# Mynd_USB_JACK.net
KiCad netlist of a schematic drawn in Altium Designer
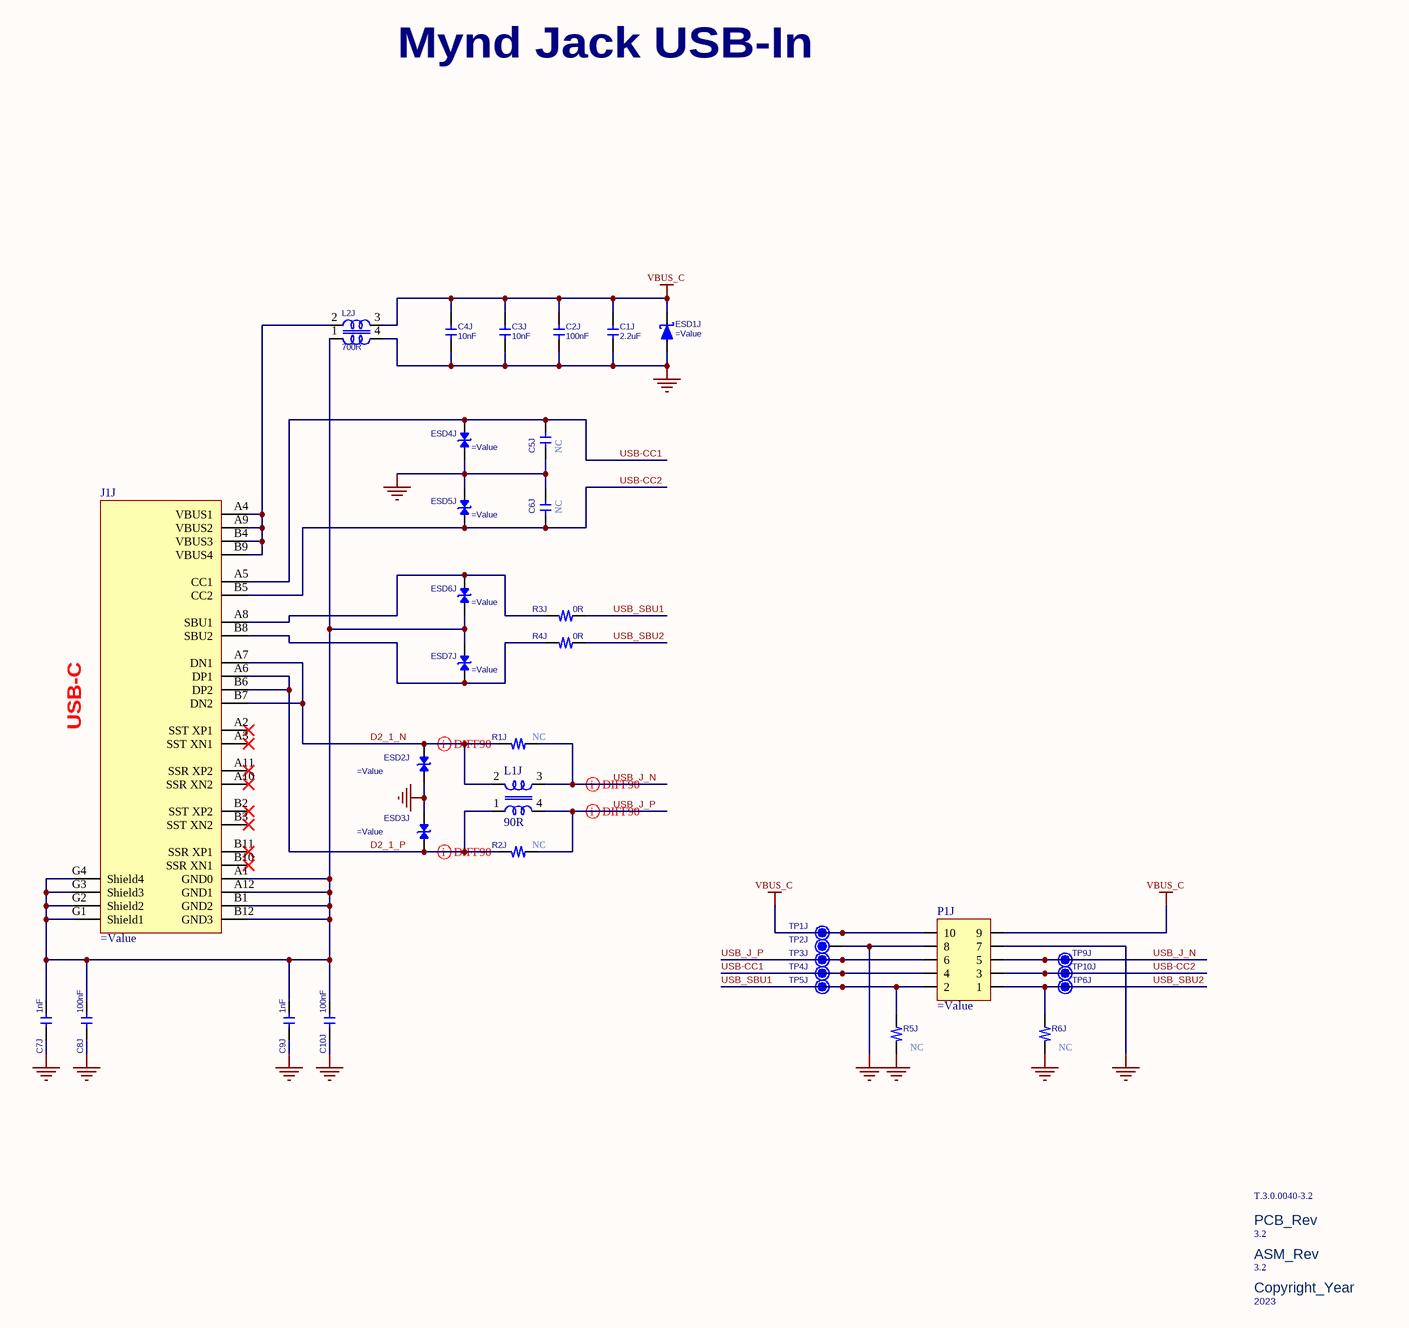
[diagram p0: Mynd_USB_JACK.SchDoc]

(export (version "E")
  (design (tool "Eeschema 10.0.6"))
  (components
    (comp (ref "C1J")
      (value "2.2uF")
      (footprint "C0805_145")
      (description "GPHF $ SMD M CAP 2.2uF 50V ±10% 0805 X5R")
      (fields (field (name "MANUFACTURER") "Multi-Sourced") (field (name "TOLERANCE") "±10%"))
      (libsource (lib "altium-import") (part "root_3_CAP1_"))
    )
    (comp (ref "C2J")
      (value "100nF")
      (footprint "C0603X100")
      (description "GPHF SMD M CAP 100nF 50V ±10% 0603 X7R")
      (fields (field (name "MANUFACTURER") "Multi-Sourced") (field (name "TOLERANCE") "±10%"))
      (libsource (lib "altium-import") (part "root_3_CAP1_"))
    )
    (comp (ref "C3J")
      (value "10nF")
      (footprint "C0603X100")
      (description "PSHF SMD M CAP 10nF 50V ±10% 0603 X7R")
      (fields (field (name "MANUFACTURER") "Multi-Sourced") (field (name "TOLERANCE") "±10%"))
      (libsource (lib "altium-import") (part "root_3_CAP1_"))
    )
    (comp (ref "C4J")
      (value "10nF")
      (footprint "C0603X100")
      (description "PSHF SMD M CAP 10nF 50V ±10% 0603 X7R")
      (fields (field (name "MANUFACTURER") "Multi-Sourced") (field (name "TOLERANCE") "±10%"))
      (libsource (lib "altium-import") (part "root_3_CAP1_"))
    )
    (comp (ref "C5J")
      (value "470pF")
      (footprint "C0603X80")
      (description "PSHF SMD CAP 470pF 50V 10%")
      (fields (field (name "MANUFACTURER") "Multi-Sourced") (field (name "TOLERANCE") "±10%"))
      (libsource (lib "altium-import") (part "root_3_CAP1_"))
    )
    (comp (ref "C6J")
      (value "470pF")
      (footprint "C0603X80")
      (description "PSHF SMD CAP 470pF 50V 10%")
      (fields (field (name "MANUFACTURER") "Multi-Sourced") (field (name "TOLERANCE") "±10%"))
      (libsource (lib "altium-import") (part "root_1_CAP1_"))
    )
    (comp (ref "C7J")
      (value "1nF")
      (footprint "C0603X100")
      (description "GPHF SMD M CAP 1nF 50V ±10% 0603 X7R")
      (fields (field (name "MANUFACTURER") "Multi-Sourced") (field (name "TOLERANCE") "±10%"))
      (libsource (lib "altium-import") (part "root_3_CAP1_"))
    )
    (comp (ref "C8J")
      (value "100nF")
      (footprint "C0603X100")
      (description "GPHF SMD M CAP 100nF 50V ±10% 0603 X7R")
      (fields (field (name "MANUFACTURER") "Multi-Sourced") (field (name "TOLERANCE") "±10%"))
      (libsource (lib "altium-import") (part "root_3_CAP1_"))
    )
    (comp (ref "C9J")
      (value "1nF")
      (footprint "C0603X100")
      (description "GPHF SMD M CAP 1nF 50V ±10% 0603 X7R")
      (fields (field (name "MANUFACTURER") "Multi-Sourced") (field (name "TOLERANCE") "±10%"))
      (libsource (lib "altium-import") (part "root_3_CAP1_"))
    )
    (comp (ref "C10J")
      (value "100nF")
      (footprint "C0603X100")
      (description "GPHF SMD M CAP 100nF 50V ±10% 0603 X7R")
      (fields (field (name "MANUFACTURER") "Multi-Sourced") (field (name "TOLERANCE") "±10%"))
      (libsource (lib "altium-import") (part "root_3_CAP1_"))
    )
    (comp (ref "ESD1J")
      (value "~")
      (footprint "SOD-123FL")
      (description "SMD TVS 2P 26 SOD-123FL SMF26AL JJW")
      (fields (field (name "MANUFACTURER") "JJW") (field (name "VOLTAGE") "26"))
      (libsource (lib "altium-import") (part "root_1_mirrored_DIODE_TVS1_"))
    )
    (comp (ref "ESD2J")
      (value "~")
      (footprint "DFN2_100X60X50_65")
      (description "SMD TVS 2P 5.5 DFN1006 CESD0501CU CTE")
      (fields (field (name "MANUFACTURER") "CTE") (field (name "VOLTAGE") "5.5V"))
      (libsource (lib "altium-import") (part "root_1_mirrored_DIODE_BID_ESD2_"))
    )
    (comp (ref "ESD3J")
      (value "~")
      (footprint "DFN2_100X60X50_65")
      (description "SMD TVS 2P 5.5 DFN1006 CESD0501CU CTE")
      (fields (field (name "MANUFACTURER") "CTE") (field (name "VOLTAGE") "5.5V"))
      (libsource (lib "altium-import") (part "root_3_mirrored_DIODE_BID_ESD2_"))
    )
    (comp (ref "ESD4J")
      (value "~")
      (footprint "DFN2_100X60X50_65")
      (description "SMD TVS 2P 5.5 DFN1006 CESD0501CU CTE")
      (fields (field (name "MANUFACTURER") "CTE") (field (name "VOLTAGE") "5.5V"))
      (libsource (lib "altium-import") (part "root_3_mirrored_DIODE_BID_ESD2_"))
    )
    (comp (ref "ESD5J")
      (value "~")
      (footprint "DFN2_100X60X50_65")
      (description "SMD TVS 2P 5.5 DFN1006 CESD0501CU CTE")
      (fields (field (name "MANUFACTURER") "CTE") (field (name "VOLTAGE") "5.5V"))
      (libsource (lib "altium-import") (part "root_1_mirrored_DIODE_BID_ESD2_"))
    )
    (comp (ref "ESD6J")
      (value "~")
      (footprint "DFN2_100X60X50_65")
      (description "SMD TVS 2P 5.5 DFN1006 CESD0501CU CTE")
      (fields (field (name "MANUFACTURER") "CTE") (field (name "VOLTAGE") "5.5V"))
      (libsource (lib "altium-import") (part "root_1_mirrored_DIODE_BID_ESD2_"))
    )
    (comp (ref "ESD7J")
      (value "~")
      (footprint "DFN2_100X60X50_65")
      (description "SMD TVS 2P 5.5 DFN1006 CESD0501CU CTE")
      (fields (field (name "MANUFACTURER") "CTE") (field (name "VOLTAGE") "5.5V"))
      (libsource (lib "altium-import") (part "root_3_mirrored_DIODE_BID_ESD2_"))
    )
    (comp (ref "J1J")
      (value "~")
      (footprint "USB_TYPE_C_HC_0768")
      (description "SMD USB JACK 24P TID VERIFY")
      (fields (field (name "MANUFACTURER") "FTS") (field (name "PART_NUMBER") "NG-HC-0412"))
      (libsource (lib "altium-import") (part "root_0_mirrored_USB_TYPE_C_3_"))
    )
    (comp (ref "L1J")
      (value "90R")
      (footprint "CET2012D")
      (description "COMMON MODE COIL 90Ohm 100MHz 400mA")
      (fields (field (name "MANUFACTURER") "CET CHAMPI") (field (name "PART_NUMBER") "CET2012A-900S"))
      (libsource (lib "altium-import") (part "root_2_mirrored_CET9070F-701_"))
    )
    (comp (ref "L2J")
      (value "700R")
      (footprint "DU_IND_SMD_SCM7060")
      (description "GPCOMMON MODE COIL 700Ohm 100MHz 125V 4A")
      (fields (field (name "MANUFACTURER") "CET CHAMPI") (field (name "VOLTAGE") "125V"))
      (libsource (lib "altium-import") (part "root_2_mirrored_INDUCTOR_CM_2_"))
    )
    (comp (ref "P1J")
      (value "~")
      (footprint "WB200AW_2x5P")
      (description "SMD WTB CONNECTOR 10P P2.0mm TIN")
      (fields (field (name "MANUFACTURER") "MINGHENG") (field (name "PART_NUMBER") "WB200AW-10"))
      (libsource (lib "altium-import") (part "root_2_CON 2X5P_"))
    )
    (comp (ref "R1J")
      (value "0R")
      (footprint "R0402")
      (description "SMD THICK FILM RES. 0Ohm 1/16W 1% 0402")
      (fields (field (name "MANUFACTURER") "Multi-Sourced") (field (name "TOLERANCE") "1%"))
      (libsource (lib "altium-import") (part "root_0_RES1_"))
    )
    (comp (ref "R2J")
      (value "0R")
      (footprint "R0402")
      (description "SMD THICK FILM RES. 0Ohm 1/16W 1% 0402")
      (fields (field (name "MANUFACTURER") "Multi-Sourced") (field (name "TOLERANCE") "1%"))
      (libsource (lib "altium-import") (part "root_0_RES1_"))
    )
    (comp (ref "R3J")
      (value "0R")
      (footprint "R0402")
      (description "GPHF SMD RES. 0OHM 1/16W 5% 0402")
      (fields (field (name "MANUFACTURER") "Multi-Sourced") (field (name "TOLERANCE") "5%"))
      (libsource (lib "altium-import") (part "root_0_RES1_"))
    )
    (comp (ref "R4J")
      (value "0R")
      (footprint "R0402")
      (description "GPHF SMD RES. 0OHM 1/16W 5% 0402")
      (fields (field (name "MANUFACTURER") "Multi-Sourced") (field (name "TOLERANCE") "5%"))
      (libsource (lib "altium-import") (part "root_0_RES1_"))
    )
    (comp (ref "R5J")
      (value "NC")
      (footprint "R0402")
      (description "SMD THICK FILM RES. 0Ohm 1/16W 1% 0402")
      (fields (field (name "MANUFACTURER") "Multi-Sourced") (field (name "TOLERANCE") "1%"))
      (libsource (lib "altium-import") (part "root_1_RES1_"))
    )
    (comp (ref "R6J")
      (value "NC")
      (footprint "R0402")
      (description "SMD THICK FILM RES. 0Ohm 1/16W 1% 0402")
      (fields (field (name "MANUFACTURER") "Multi-Sourced") (field (name "TOLERANCE") "1%"))
      (libsource (lib "altium-import") (part "root_1_RES1_"))
    )
    (comp (ref "Teufel_ASM_Label1J")
      (value "=SCH_REV")
      (footprint "Teufel_ASM_Rev")
      (description "Teufel_ASM_Rev")
      (libsource (lib "altium-import") (part "root_0_Teufel_ASM_Label_"))
    )
    (comp (ref "Teufel_Copyright1K")
      (value "~")
      (footprint "TEUFEL_COPYRIGHT")
      (description "Teufel_Copyright_Year")
      (libsource (lib "altium-import") (part "root_0_Teufel_Copyright_"))
    )
    (comp (ref "Teufel_PCB_Label1J")
      (value "=SCH_REV")
      (footprint "Teufel_PCB_Rev")
      (description "Teufel_PCB_Label")
      (libsource (lib "altium-import") (part "root_0_Teufel_PCB_Label_"))
    )
    (comp (ref "Teufel_PCB_Logo1k")
      (value "-=SCH_REV")
      (footprint "Teufel_NoLogo")
      (description "Teufel PCB NoLogo")
      (libsource (lib "altium-import") (part "root_0_Teufel NoLogo_"))
    )
    (comp (ref "TP1J")
      (value "TP12")
      (footprint "TP120")
      (description "Test Point")
      (libsource (lib "altium-import") (part "root_2_TP_"))
    )
    (comp (ref "TP2J")
      (value "TP12")
      (footprint "TP120")
      (description "Test Point")
      (libsource (lib "altium-import") (part "root_2_TP_"))
    )
    (comp (ref "TP3J")
      (value "TP12")
      (footprint "TP120")
      (description "Test Point")
      (libsource (lib "altium-import") (part "root_2_TP_"))
    )
    (comp (ref "TP4J")
      (value "TP12")
      (footprint "TP120")
      (description "Test Point")
      (libsource (lib "altium-import") (part "root_2_TP_"))
    )
    (comp (ref "TP5J")
      (value "TP12")
      (footprint "TP120")
      (description "Test Point")
      (libsource (lib "altium-import") (part "root_2_TP_"))
    )
    (comp (ref "TP6J")
      (value "TP12")
      (footprint "TP120")
      (description "Test Point")
      (libsource (lib "altium-import") (part "root_2_mirrored_TP_"))
    )
    (comp (ref "TP9J")
      (value "TP12")
      (footprint "TP120")
      (description "Test Point")
      (libsource (lib "altium-import") (part "root_2_mirrored_TP_"))
    )
    (comp (ref "TP10J")
      (value "TP12")
      (footprint "TP120")
      (description "Test Point")
      (libsource (lib "altium-import") (part "root_2_mirrored_TP_"))
    )
  )
  (nets
    (net (code "1") (name "/D2_1_N") (class "Default")
      (node (ref "ESD2J") (pin "2") (pinfunction "2_2") (pintype "passive"))
      (node (ref "J1J") (pin "A7") (pinfunction "DN1_A7") (pintype "passive"))
      (node (ref "J1J") (pin "B7") (pinfunction "DN2_B7") (pintype "passive"))
      (node (ref "L1J") (pin "2") (pinfunction "2_2") (pintype "passive"))
      (node (ref "R1J") (pin "1") (pinfunction "1_1") (pintype "passive"))
    )
    (net (code "2") (name "/D2_1_P") (class "Default")
      (node (ref "ESD3J") (pin "2") (pinfunction "2_2") (pintype "passive"))
      (node (ref "J1J") (pin "A6") (pinfunction "DP1_A6") (pintype "passive"))
      (node (ref "J1J") (pin "B6") (pinfunction "DP2_B6") (pintype "passive"))
      (node (ref "L1J") (pin "1") (pinfunction "1_1") (pintype "passive"))
      (node (ref "R2J") (pin "1") (pinfunction "1_1") (pintype "passive"))
    )
    (net (code "3") (name "/USB-CC1") (class "Default")
      (node (ref "C5J") (pin "1") (pinfunction "1_1") (pintype "passive"))
      (node (ref "ESD4J") (pin "1") (pinfunction "1_1") (pintype "passive"))
      (node (ref "J1J") (pin "A5") (pinfunction "CC1_A5") (pintype "passive"))
      (node (ref "P1J") (pin "4") (pinfunction "4_4") (pintype "passive"))
      (node (ref "TP4J") (pin "1") (pinfunction "1_1") (pintype "passive"))
    )
    (net (code "4") (name "/USB-CC2") (class "Default")
      (node (ref "C6J") (pin "1") (pinfunction "1_1") (pintype "passive"))
      (node (ref "ESD5J") (pin "1") (pinfunction "1_1") (pintype "passive"))
      (node (ref "J1J") (pin "B5") (pinfunction "CC2_B5") (pintype "passive"))
      (node (ref "P1J") (pin "3") (pinfunction "3_3") (pintype "passive"))
      (node (ref "TP10J") (pin "1") (pinfunction "1_1") (pintype "passive"))
    )
    (net (code "5") (name "/USB_J_N") (class "Default")
      (node (ref "L1J") (pin "3") (pinfunction "3_3") (pintype "passive"))
      (node (ref "P1J") (pin "5") (pinfunction "5_5") (pintype "passive"))
      (node (ref "R1J") (pin "2") (pinfunction "2_2") (pintype "passive"))
      (node (ref "TP9J") (pin "1") (pinfunction "1_1") (pintype "passive"))
    )
    (net (code "6") (name "/USB_J_P") (class "Default")
      (node (ref "L1J") (pin "4") (pinfunction "4_4") (pintype "passive"))
      (node (ref "P1J") (pin "6") (pinfunction "6_6") (pintype "passive"))
      (node (ref "R2J") (pin "2") (pinfunction "2_2") (pintype "passive"))
      (node (ref "TP3J") (pin "1") (pinfunction "1_1") (pintype "passive"))
    )
    (net (code "7") (name "/USB_SBU1") (class "Default")
      (node (ref "P1J") (pin "2") (pinfunction "2_2") (pintype "passive"))
      (node (ref "R3J") (pin "2") (pinfunction "2_2") (pintype "passive"))
      (node (ref "R5J") (pin "2") (pinfunction "2_2") (pintype "passive"))
      (node (ref "TP5J") (pin "1") (pinfunction "1_1") (pintype "passive"))
    )
    (net (code "8") (name "/USB_SBU2") (class "Default")
      (node (ref "P1J") (pin "1") (pinfunction "1_1") (pintype "passive"))
      (node (ref "R4J") (pin "2") (pinfunction "2_2") (pintype "passive"))
      (node (ref "R6J") (pin "2") (pinfunction "2_2") (pintype "passive"))
      (node (ref "TP6J") (pin "1") (pinfunction "1_1") (pintype "passive"))
    )
    (net (code "9") (name "GND") (class "Default")
      (node (ref "C10J") (pin "2") (pinfunction "2_2") (pintype "passive"))
      (node (ref "C1J") (pin "2") (pinfunction "2_2") (pintype "passive"))
      (node (ref "C2J") (pin "2") (pinfunction "2_2") (pintype "passive"))
      (node (ref "C3J") (pin "2") (pinfunction "2_2") (pintype "passive"))
      (node (ref "C4J") (pin "2") (pinfunction "2_2") (pintype "passive"))
      (node (ref "C5J") (pin "2") (pinfunction "2_2") (pintype "passive"))
      (node (ref "C6J") (pin "2") (pinfunction "2_2") (pintype "passive"))
      (node (ref "C7J") (pin "2") (pinfunction "2_2") (pintype "passive"))
      (node (ref "C8J") (pin "2") (pinfunction "2_2") (pintype "passive"))
      (node (ref "C9J") (pin "2") (pinfunction "2_2") (pintype "passive"))
      (node (ref "ESD1J") (pin "A") (pinfunction "A_A") (pintype "passive"))
      (node (ref "ESD2J") (pin "1") (pinfunction "1_1") (pintype "passive"))
      (node (ref "ESD3J") (pin "1") (pinfunction "1_1") (pintype "passive"))
      (node (ref "ESD4J") (pin "2") (pinfunction "2_2") (pintype "passive"))
      (node (ref "ESD5J") (pin "2") (pinfunction "2_2") (pintype "passive"))
      (node (ref "L2J") (pin "4") (pinfunction "4_4") (pintype "passive"))
      (node (ref "P1J") (pin "7") (pinfunction "7_7") (pintype "passive"))
      (node (ref "P1J") (pin "8") (pinfunction "8_8") (pintype "passive"))
      (node (ref "R5J") (pin "1") (pinfunction "1_1") (pintype "passive"))
      (node (ref "R6J") (pin "1") (pinfunction "1_1") (pintype "passive"))
      (node (ref "TP2J") (pin "1") (pinfunction "1_1") (pintype "passive"))
    )
    (net (code "10") (name "Net-(J1J-GND0)") (class "Default")
      (node (ref "C10J") (pin "1") (pinfunction "1_1") (pintype "passive"))
      (node (ref "C7J") (pin "1") (pinfunction "1_1") (pintype "passive"))
      (node (ref "C8J") (pin "1") (pinfunction "1_1") (pintype "passive"))
      (node (ref "C9J") (pin "1") (pinfunction "1_1") (pintype "passive"))
      (node (ref "ESD6J") (pin "1") (pinfunction "1_1") (pintype "passive"))
      (node (ref "ESD7J") (pin "1") (pinfunction "1_1") (pintype "passive"))
      (node (ref "J1J") (pin "A1") (pinfunction "GND0_A1") (pintype "passive"))
      (node (ref "J1J") (pin "A12") (pinfunction "GND1_A12") (pintype "passive"))
      (node (ref "J1J") (pin "B1") (pinfunction "GND2_B1") (pintype "passive"))
      (node (ref "J1J") (pin "B12") (pinfunction "GND3_B12") (pintype "passive"))
      (node (ref "J1J") (pin "G1") (pinfunction "Shield1_G1") (pintype "passive"))
      (node (ref "J1J") (pin "G2") (pinfunction "Shield2_G2") (pintype "passive"))
      (node (ref "J1J") (pin "G3") (pinfunction "Shield3_G3") (pintype "passive"))
      (node (ref "J1J") (pin "G4") (pinfunction "Shield4_G4") (pintype "passive"))
      (node (ref "L2J") (pin "1") (pinfunction "1_1") (pintype "passive"))
    )
    (net (code "11") (name "Net-(J1J-SBU1)") (class "Default")
      (node (ref "ESD6J") (pin "2") (pinfunction "2_2") (pintype "passive"))
      (node (ref "J1J") (pin "A8") (pinfunction "SBU1_A8") (pintype "passive"))
      (node (ref "R3J") (pin "1") (pinfunction "1_1") (pintype "passive"))
    )
    (net (code "12") (name "Net-(J1J-SBU2)") (class "Default")
      (node (ref "ESD7J") (pin "2") (pinfunction "2_2") (pintype "passive"))
      (node (ref "J1J") (pin "B8") (pinfunction "SBU2_B8") (pintype "passive"))
      (node (ref "R4J") (pin "1") (pinfunction "1_1") (pintype "passive"))
    )
    (net (code "13") (name "Net-(J1J-VBUS1)") (class "Default")
      (node (ref "J1J") (pin "A4") (pinfunction "VBUS1_A4") (pintype "passive"))
      (node (ref "J1J") (pin "A9") (pinfunction "VBUS2_A9") (pintype "passive"))
      (node (ref "J1J") (pin "B4") (pinfunction "VBUS3_B4") (pintype "passive"))
      (node (ref "J1J") (pin "B9") (pinfunction "VBUS4_B9") (pintype "passive"))
      (node (ref "L2J") (pin "2") (pinfunction "2_2") (pintype "passive"))
    )
    (net (code "14") (name "VBUS_C") (class "Default")
      (node (ref "C1J") (pin "1") (pinfunction "1_1") (pintype "passive"))
      (node (ref "C2J") (pin "1") (pinfunction "1_1") (pintype "passive"))
      (node (ref "C3J") (pin "1") (pinfunction "1_1") (pintype "passive"))
      (node (ref "C4J") (pin "1") (pinfunction "1_1") (pintype "passive"))
      (node (ref "ESD1J") (pin "K") (pinfunction "K_K") (pintype "passive"))
      (node (ref "L2J") (pin "3") (pinfunction "3_3") (pintype "passive"))
      (node (ref "P1J") (pin "10") (pinfunction "10_10") (pintype "passive"))
      (node (ref "P1J") (pin "9") (pinfunction "9_9") (pintype "passive"))
      (node (ref "TP1J") (pin "1") (pinfunction "1_1") (pintype "passive"))
    )
    (net (code "15") (name "unconnected-(J1J-SSR_XN1-PadB10)") (class "Default")
      (node (ref "J1J") (pin "B10") (pinfunction "SSR_XN1_B10") (pintype "passive+no_connect"))
    )
    (net (code "16") (name "unconnected-(J1J-SSR_XN2-PadA10)") (class "Default")
      (node (ref "J1J") (pin "A10") (pinfunction "SSR_XN2_A10") (pintype "passive+no_connect"))
    )
    (net (code "17") (name "unconnected-(J1J-SSR_XP1-PadB11)") (class "Default")
      (node (ref "J1J") (pin "B11") (pinfunction "SSR_XP1_B11") (pintype "passive+no_connect"))
    )
    (net (code "18") (name "unconnected-(J1J-SSR_XP2-PadA11)") (class "Default")
      (node (ref "J1J") (pin "A11") (pinfunction "SSR_XP2_A11") (pintype "passive+no_connect"))
    )
    (net (code "19") (name "unconnected-(J1J-SST_XN1-PadA3)") (class "Default")
      (node (ref "J1J") (pin "A3") (pinfunction "SST_XN1_A3") (pintype "passive+no_connect"))
    )
    (net (code "20") (name "unconnected-(J1J-SST_XN2-PadB3)") (class "Default")
      (node (ref "J1J") (pin "B3") (pinfunction "SST_XN2_B3") (pintype "passive+no_connect"))
    )
    (net (code "21") (name "unconnected-(J1J-SST_XP1-PadA2)") (class "Default")
      (node (ref "J1J") (pin "A2") (pinfunction "SST_XP1_A2") (pintype "passive+no_connect"))
    )
    (net (code "22") (name "unconnected-(J1J-SST_XP2-PadB2)") (class "Default")
      (node (ref "J1J") (pin "B2") (pinfunction "SST_XP2_B2") (pintype "passive+no_connect"))
    )
  )
)
